# BitALU.net
KiCad netlist of a schematic drawn in EAGLE
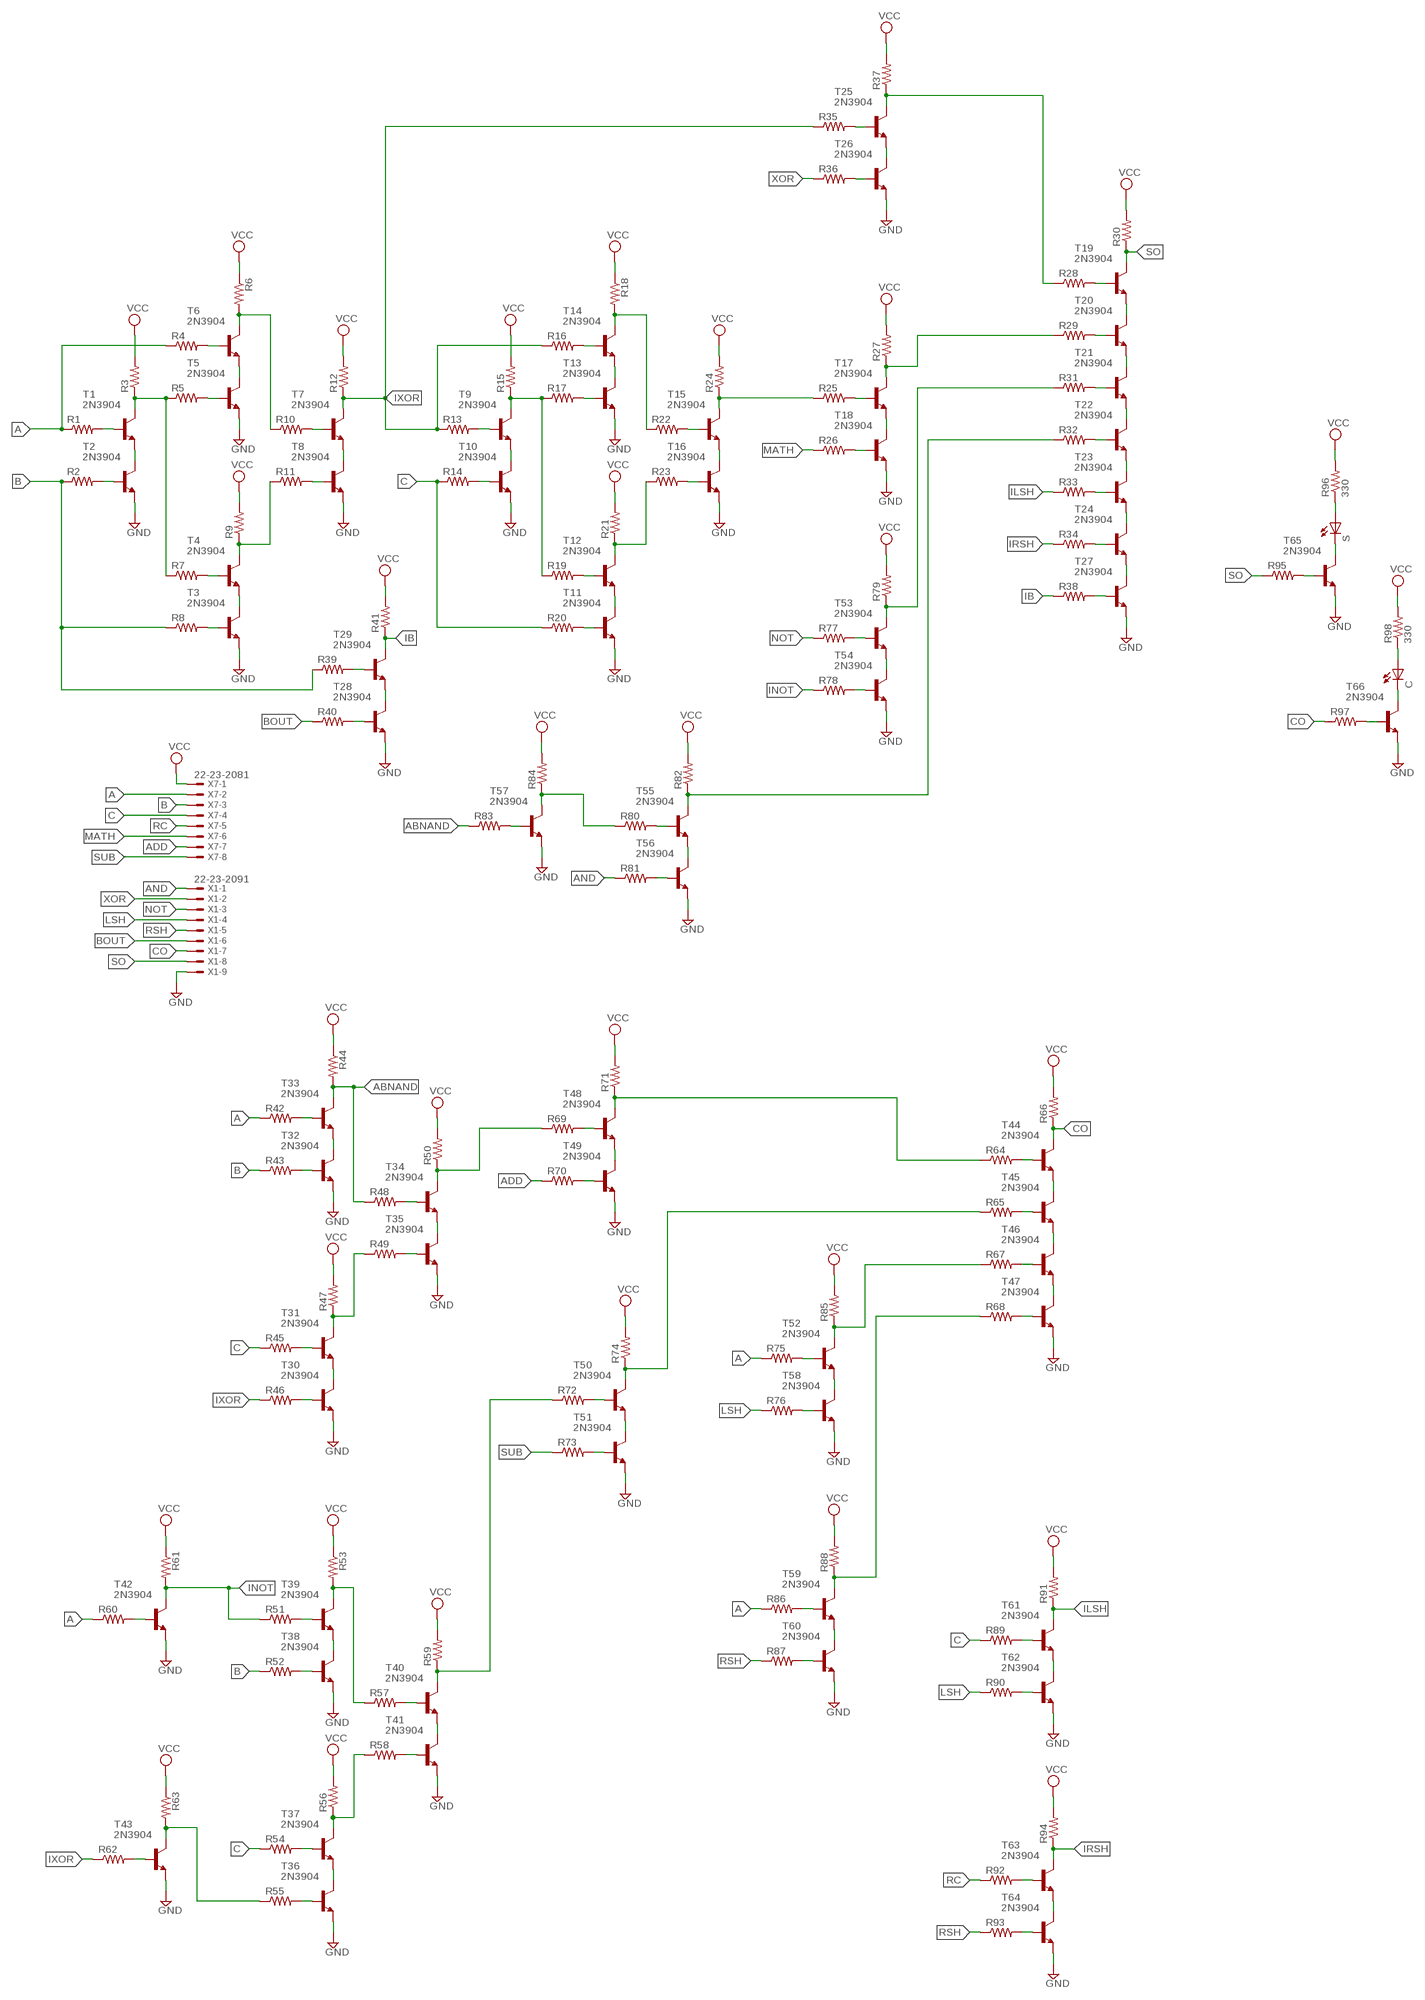
[diagram p0: schematic, sheet 1]

(export (version "E")
  (design (tool "Eeschema 10.0.6"))
  (components
    (comp (ref "C")
      (value "LED5MM")
      (footprint "eagle-import:LED5MM")
      (libsource (lib "eagle-import") (part "LED5MM"))
    )
    (comp (ref "R1")
      (value "R-US_0309/10")
      (footprint "eagle-import:0309_10")
      (libsource (lib "eagle-import") (part "R-US_0309/10"))
    )
    (comp (ref "R2")
      (value "R-US_0309/10")
      (footprint "eagle-import:0309_10")
      (libsource (lib "eagle-import") (part "R-US_0309/10"))
    )
    (comp (ref "R3")
      (value "R-US_0309/10")
      (footprint "eagle-import:0309_10")
      (libsource (lib "eagle-import") (part "R-US_0309/10"))
    )
    (comp (ref "R4")
      (value "R-US_0309/10")
      (footprint "eagle-import:0309_10")
      (libsource (lib "eagle-import") (part "R-US_0309/10"))
    )
    (comp (ref "R5")
      (value "R-US_0309/10")
      (footprint "eagle-import:0309_10")
      (libsource (lib "eagle-import") (part "R-US_0309/10"))
    )
    (comp (ref "R6")
      (value "R-US_0309/10")
      (footprint "eagle-import:0309_10")
      (libsource (lib "eagle-import") (part "R-US_0309/10"))
    )
    (comp (ref "R7")
      (value "R-US_0309/10")
      (footprint "eagle-import:0309_10")
      (libsource (lib "eagle-import") (part "R-US_0309/10"))
    )
    (comp (ref "R8")
      (value "R-US_0309/10")
      (footprint "eagle-import:0309_10")
      (libsource (lib "eagle-import") (part "R-US_0309/10"))
    )
    (comp (ref "R9")
      (value "R-US_0309/10")
      (footprint "eagle-import:0309_10")
      (libsource (lib "eagle-import") (part "R-US_0309/10"))
    )
    (comp (ref "R10")
      (value "R-US_0309/10")
      (footprint "eagle-import:0309_10")
      (libsource (lib "eagle-import") (part "R-US_0309/10"))
    )
    (comp (ref "R11")
      (value "R-US_0309/10")
      (footprint "eagle-import:0309_10")
      (libsource (lib "eagle-import") (part "R-US_0309/10"))
    )
    (comp (ref "R12")
      (value "R-US_0309/10")
      (footprint "eagle-import:0309_10")
      (libsource (lib "eagle-import") (part "R-US_0309/10"))
    )
    (comp (ref "R13")
      (value "R-US_0309/10")
      (footprint "eagle-import:0309_10")
      (libsource (lib "eagle-import") (part "R-US_0309/10"))
    )
    (comp (ref "R14")
      (value "R-US_0309/10")
      (footprint "eagle-import:0309_10")
      (libsource (lib "eagle-import") (part "R-US_0309/10"))
    )
    (comp (ref "R15")
      (value "R-US_0309/10")
      (footprint "eagle-import:0309_10")
      (libsource (lib "eagle-import") (part "R-US_0309/10"))
    )
    (comp (ref "R16")
      (value "R-US_0309/10")
      (footprint "eagle-import:0309_10")
      (libsource (lib "eagle-import") (part "R-US_0309/10"))
    )
    (comp (ref "R17")
      (value "R-US_0309/10")
      (footprint "eagle-import:0309_10")
      (libsource (lib "eagle-import") (part "R-US_0309/10"))
    )
    (comp (ref "R18")
      (value "R-US_0309/10")
      (footprint "eagle-import:0309_10")
      (libsource (lib "eagle-import") (part "R-US_0309/10"))
    )
    (comp (ref "R19")
      (value "R-US_0309/10")
      (footprint "eagle-import:0309_10")
      (libsource (lib "eagle-import") (part "R-US_0309/10"))
    )
    (comp (ref "R20")
      (value "R-US_0309/10")
      (footprint "eagle-import:0309_10")
      (libsource (lib "eagle-import") (part "R-US_0309/10"))
    )
    (comp (ref "R21")
      (value "R-US_0309/10")
      (footprint "eagle-import:0309_10")
      (libsource (lib "eagle-import") (part "R-US_0309/10"))
    )
    (comp (ref "R22")
      (value "R-US_0309/10")
      (footprint "eagle-import:0309_10")
      (libsource (lib "eagle-import") (part "R-US_0309/10"))
    )
    (comp (ref "R23")
      (value "R-US_0309/10")
      (footprint "eagle-import:0309_10")
      (libsource (lib "eagle-import") (part "R-US_0309/10"))
    )
    (comp (ref "R24")
      (value "R-US_0309/10")
      (footprint "eagle-import:0309_10")
      (libsource (lib "eagle-import") (part "R-US_0309/10"))
    )
    (comp (ref "R25")
      (value "R-US_0309/10")
      (footprint "eagle-import:0309_10")
      (libsource (lib "eagle-import") (part "R-US_0309/10"))
    )
    (comp (ref "R26")
      (value "R-US_0309/10")
      (footprint "eagle-import:0309_10")
      (libsource (lib "eagle-import") (part "R-US_0309/10"))
    )
    (comp (ref "R27")
      (value "R-US_0309/10")
      (footprint "eagle-import:0309_10")
      (libsource (lib "eagle-import") (part "R-US_0309/10"))
    )
    (comp (ref "R28")
      (value "R-US_0309/10")
      (footprint "eagle-import:0309_10")
      (libsource (lib "eagle-import") (part "R-US_0309/10"))
    )
    (comp (ref "R29")
      (value "R-US_0309/10")
      (footprint "eagle-import:0309_10")
      (libsource (lib "eagle-import") (part "R-US_0309/10"))
    )
    (comp (ref "R30")
      (value "R-US_0309/10")
      (footprint "eagle-import:0309_10")
      (libsource (lib "eagle-import") (part "R-US_0309/10"))
    )
    (comp (ref "R31")
      (value "R-US_0309/10")
      (footprint "eagle-import:0309_10")
      (libsource (lib "eagle-import") (part "R-US_0309/10"))
    )
    (comp (ref "R32")
      (value "R-US_0309/10")
      (footprint "eagle-import:0309_10")
      (libsource (lib "eagle-import") (part "R-US_0309/10"))
    )
    (comp (ref "R33")
      (value "R-US_0309/10")
      (footprint "eagle-import:0309_10")
      (libsource (lib "eagle-import") (part "R-US_0309/10"))
    )
    (comp (ref "R34")
      (value "R-US_0309/10")
      (footprint "eagle-import:0309_10")
      (libsource (lib "eagle-import") (part "R-US_0309/10"))
    )
    (comp (ref "R35")
      (value "R-US_0309/10")
      (footprint "eagle-import:0309_10")
      (libsource (lib "eagle-import") (part "R-US_0309/10"))
    )
    (comp (ref "R36")
      (value "R-US_0309/10")
      (footprint "eagle-import:0309_10")
      (libsource (lib "eagle-import") (part "R-US_0309/10"))
    )
    (comp (ref "R37")
      (value "R-US_0309/10")
      (footprint "eagle-import:0309_10")
      (libsource (lib "eagle-import") (part "R-US_0309/10"))
    )
    (comp (ref "R38")
      (value "R-US_0309/10")
      (footprint "eagle-import:0309_10")
      (libsource (lib "eagle-import") (part "R-US_0309/10"))
    )
    (comp (ref "R39")
      (value "R-US_0309/10")
      (footprint "eagle-import:0309_10")
      (libsource (lib "eagle-import") (part "R-US_0309/10"))
    )
    (comp (ref "R40")
      (value "R-US_0309/10")
      (footprint "eagle-import:0309_10")
      (libsource (lib "eagle-import") (part "R-US_0309/10"))
    )
    (comp (ref "R41")
      (value "R-US_0309/10")
      (footprint "eagle-import:0309_10")
      (libsource (lib "eagle-import") (part "R-US_0309/10"))
    )
    (comp (ref "R42")
      (value "R-US_0309/10")
      (footprint "eagle-import:0309_10")
      (libsource (lib "eagle-import") (part "R-US_0309/10"))
    )
    (comp (ref "R43")
      (value "R-US_0309/10")
      (footprint "eagle-import:0309_10")
      (libsource (lib "eagle-import") (part "R-US_0309/10"))
    )
    (comp (ref "R44")
      (value "R-US_0309/10")
      (footprint "eagle-import:0309_10")
      (libsource (lib "eagle-import") (part "R-US_0309/10"))
    )
    (comp (ref "R45")
      (value "R-US_0309/10")
      (footprint "eagle-import:0309_10")
      (libsource (lib "eagle-import") (part "R-US_0309/10"))
    )
    (comp (ref "R46")
      (value "R-US_0309/10")
      (footprint "eagle-import:0309_10")
      (libsource (lib "eagle-import") (part "R-US_0309/10"))
    )
    (comp (ref "R47")
      (value "R-US_0309/10")
      (footprint "eagle-import:0309_10")
      (libsource (lib "eagle-import") (part "R-US_0309/10"))
    )
    (comp (ref "R48")
      (value "R-US_0309/10")
      (footprint "eagle-import:0309_10")
      (libsource (lib "eagle-import") (part "R-US_0309/10"))
    )
    (comp (ref "R49")
      (value "R-US_0309/10")
      (footprint "eagle-import:0309_10")
      (libsource (lib "eagle-import") (part "R-US_0309/10"))
    )
    (comp (ref "R50")
      (value "R-US_0309/10")
      (footprint "eagle-import:0309_10")
      (libsource (lib "eagle-import") (part "R-US_0309/10"))
    )
    (comp (ref "R51")
      (value "R-US_0309/10")
      (footprint "eagle-import:0309_10")
      (libsource (lib "eagle-import") (part "R-US_0309/10"))
    )
    (comp (ref "R52")
      (value "R-US_0309/10")
      (footprint "eagle-import:0309_10")
      (libsource (lib "eagle-import") (part "R-US_0309/10"))
    )
    (comp (ref "R53")
      (value "R-US_0309/10")
      (footprint "eagle-import:0309_10")
      (libsource (lib "eagle-import") (part "R-US_0309/10"))
    )
    (comp (ref "R54")
      (value "R-US_0309/10")
      (footprint "eagle-import:0309_10")
      (libsource (lib "eagle-import") (part "R-US_0309/10"))
    )
    (comp (ref "R55")
      (value "R-US_0309/10")
      (footprint "eagle-import:0309_10")
      (libsource (lib "eagle-import") (part "R-US_0309/10"))
    )
    (comp (ref "R56")
      (value "R-US_0309/10")
      (footprint "eagle-import:0309_10")
      (libsource (lib "eagle-import") (part "R-US_0309/10"))
    )
    (comp (ref "R57")
      (value "R-US_0309/10")
      (footprint "eagle-import:0309_10")
      (libsource (lib "eagle-import") (part "R-US_0309/10"))
    )
    (comp (ref "R58")
      (value "R-US_0309/10")
      (footprint "eagle-import:0309_10")
      (libsource (lib "eagle-import") (part "R-US_0309/10"))
    )
    (comp (ref "R59")
      (value "R-US_0309/10")
      (footprint "eagle-import:0309_10")
      (libsource (lib "eagle-import") (part "R-US_0309/10"))
    )
    (comp (ref "R60")
      (value "R-US_0309/10")
      (footprint "eagle-import:0309_10")
      (libsource (lib "eagle-import") (part "R-US_0309/10"))
    )
    (comp (ref "R61")
      (value "R-US_0309/10")
      (footprint "eagle-import:0309_10")
      (libsource (lib "eagle-import") (part "R-US_0309/10"))
    )
    (comp (ref "R62")
      (value "R-US_0309/10")
      (footprint "eagle-import:0309_10")
      (libsource (lib "eagle-import") (part "R-US_0309/10"))
    )
    (comp (ref "R63")
      (value "R-US_0309/10")
      (footprint "eagle-import:0309_10")
      (libsource (lib "eagle-import") (part "R-US_0309/10"))
    )
    (comp (ref "R64")
      (value "R-US_0309/10")
      (footprint "eagle-import:0309_10")
      (libsource (lib "eagle-import") (part "R-US_0309/10"))
    )
    (comp (ref "R65")
      (value "R-US_0309/10")
      (footprint "eagle-import:0309_10")
      (libsource (lib "eagle-import") (part "R-US_0309/10"))
    )
    (comp (ref "R66")
      (value "R-US_0309/10")
      (footprint "eagle-import:0309_10")
      (libsource (lib "eagle-import") (part "R-US_0309/10"))
    )
    (comp (ref "R67")
      (value "R-US_0309/10")
      (footprint "eagle-import:0309_10")
      (libsource (lib "eagle-import") (part "R-US_0309/10"))
    )
    (comp (ref "R68")
      (value "R-US_0309/10")
      (footprint "eagle-import:0309_10")
      (libsource (lib "eagle-import") (part "R-US_0309/10"))
    )
    (comp (ref "R69")
      (value "R-US_0309/10")
      (footprint "eagle-import:0309_10")
      (libsource (lib "eagle-import") (part "R-US_0309/10"))
    )
    (comp (ref "R70")
      (value "R-US_0309/10")
      (footprint "eagle-import:0309_10")
      (libsource (lib "eagle-import") (part "R-US_0309/10"))
    )
    (comp (ref "R71")
      (value "R-US_0309/10")
      (footprint "eagle-import:0309_10")
      (libsource (lib "eagle-import") (part "R-US_0309/10"))
    )
    (comp (ref "R72")
      (value "R-US_0309/10")
      (footprint "eagle-import:0309_10")
      (libsource (lib "eagle-import") (part "R-US_0309/10"))
    )
    (comp (ref "R73")
      (value "R-US_0309/10")
      (footprint "eagle-import:0309_10")
      (libsource (lib "eagle-import") (part "R-US_0309/10"))
    )
    (comp (ref "R74")
      (value "R-US_0309/10")
      (footprint "eagle-import:0309_10")
      (libsource (lib "eagle-import") (part "R-US_0309/10"))
    )
    (comp (ref "R75")
      (value "R-US_0309/10")
      (footprint "eagle-import:0309_10")
      (libsource (lib "eagle-import") (part "R-US_0309/10"))
    )
    (comp (ref "R76")
      (value "R-US_0309/10")
      (footprint "eagle-import:0309_10")
      (libsource (lib "eagle-import") (part "R-US_0309/10"))
    )
    (comp (ref "R77")
      (value "R-US_0309/10")
      (footprint "eagle-import:0309_10")
      (libsource (lib "eagle-import") (part "R-US_0309/10"))
    )
    (comp (ref "R78")
      (value "R-US_0309/10")
      (footprint "eagle-import:0309_10")
      (libsource (lib "eagle-import") (part "R-US_0309/10"))
    )
    (comp (ref "R79")
      (value "R-US_0309/10")
      (footprint "eagle-import:0309_10")
      (libsource (lib "eagle-import") (part "R-US_0309/10"))
    )
    (comp (ref "R80")
      (value "R-US_0309/10")
      (footprint "eagle-import:0309_10")
      (libsource (lib "eagle-import") (part "R-US_0309/10"))
    )
    (comp (ref "R81")
      (value "R-US_0309/10")
      (footprint "eagle-import:0309_10")
      (libsource (lib "eagle-import") (part "R-US_0309/10"))
    )
    (comp (ref "R82")
      (value "R-US_0309/10")
      (footprint "eagle-import:0309_10")
      (libsource (lib "eagle-import") (part "R-US_0309/10"))
    )
    (comp (ref "R83")
      (value "R-US_0309/10")
      (footprint "eagle-import:0309_10")
      (libsource (lib "eagle-import") (part "R-US_0309/10"))
    )
    (comp (ref "R84")
      (value "R-US_0309/10")
      (footprint "eagle-import:0309_10")
      (libsource (lib "eagle-import") (part "R-US_0309/10"))
    )
    (comp (ref "R85")
      (value "R-US_0309/10")
      (footprint "eagle-import:0309_10")
      (libsource (lib "eagle-import") (part "R-US_0309/10"))
    )
    (comp (ref "R86")
      (value "R-US_0309/10")
      (footprint "eagle-import:0309_10")
      (libsource (lib "eagle-import") (part "R-US_0309/10"))
    )
    (comp (ref "R87")
      (value "R-US_0309/10")
      (footprint "eagle-import:0309_10")
      (libsource (lib "eagle-import") (part "R-US_0309/10"))
    )
    (comp (ref "R88")
      (value "R-US_0309/10")
      (footprint "eagle-import:0309_10")
      (libsource (lib "eagle-import") (part "R-US_0309/10"))
    )
    (comp (ref "R89")
      (value "R-US_0309/10")
      (footprint "eagle-import:0309_10")
      (libsource (lib "eagle-import") (part "R-US_0309/10"))
    )
    (comp (ref "R90")
      (value "R-US_0309/10")
      (footprint "eagle-import:0309_10")
      (libsource (lib "eagle-import") (part "R-US_0309/10"))
    )
    (comp (ref "R91")
      (value "R-US_0309/10")
      (footprint "eagle-import:0309_10")
      (libsource (lib "eagle-import") (part "R-US_0309/10"))
    )
    (comp (ref "R92")
      (value "R-US_0309/10")
      (footprint "eagle-import:0309_10")
      (libsource (lib "eagle-import") (part "R-US_0309/10"))
    )
    (comp (ref "R93")
      (value "R-US_0309/10")
      (footprint "eagle-import:0309_10")
      (libsource (lib "eagle-import") (part "R-US_0309/10"))
    )
    (comp (ref "R94")
      (value "R-US_0309/10")
      (footprint "eagle-import:0309_10")
      (libsource (lib "eagle-import") (part "R-US_0309/10"))
    )
    (comp (ref "R95")
      (value "R-US_0309/10")
      (footprint "eagle-import:0309_10")
      (libsource (lib "eagle-import") (part "R-US_0309/10"))
    )
    (comp (ref "R96")
      (value "330")
      (footprint "eagle-import:0309_10")
      (libsource (lib "eagle-import") (part "R-US_0309/10"))
    )
    (comp (ref "R97")
      (value "R-US_0309/10")
      (footprint "eagle-import:0309_10")
      (libsource (lib "eagle-import") (part "R-US_0309/10"))
    )
    (comp (ref "R98")
      (value "330")
      (footprint "eagle-import:0309_10")
      (libsource (lib "eagle-import") (part "R-US_0309/10"))
    )
    (comp (ref "S")
      (value "LED5MM")
      (footprint "eagle-import:LED5MM")
      (libsource (lib "eagle-import") (part "LED5MM"))
    )
    (comp (ref "T1")
      (value "2N3904")
      (footprint "eagle-import:TO92")
      (libsource (lib "eagle-import") (part "2N3904"))
    )
    (comp (ref "T2")
      (value "2N3904")
      (footprint "eagle-import:TO92")
      (libsource (lib "eagle-import") (part "2N3904"))
    )
    (comp (ref "T3")
      (value "2N3904")
      (footprint "eagle-import:TO92")
      (libsource (lib "eagle-import") (part "2N3904"))
    )
    (comp (ref "T4")
      (value "2N3904")
      (footprint "eagle-import:TO92")
      (libsource (lib "eagle-import") (part "2N3904"))
    )
    (comp (ref "T5")
      (value "2N3904")
      (footprint "eagle-import:TO92")
      (libsource (lib "eagle-import") (part "2N3904"))
    )
    (comp (ref "T6")
      (value "2N3904")
      (footprint "eagle-import:TO92")
      (libsource (lib "eagle-import") (part "2N3904"))
    )
    (comp (ref "T7")
      (value "2N3904")
      (footprint "eagle-import:TO92")
      (libsource (lib "eagle-import") (part "2N3904"))
    )
    (comp (ref "T8")
      (value "2N3904")
      (footprint "eagle-import:TO92")
      (libsource (lib "eagle-import") (part "2N3904"))
    )
    (comp (ref "T9")
      (value "2N3904")
      (footprint "eagle-import:TO92")
      (libsource (lib "eagle-import") (part "2N3904"))
    )
    (comp (ref "T10")
      (value "2N3904")
      (footprint "eagle-import:TO92")
      (libsource (lib "eagle-import") (part "2N3904"))
    )
    (comp (ref "T11")
      (value "2N3904")
      (footprint "eagle-import:TO92")
      (libsource (lib "eagle-import") (part "2N3904"))
    )
    (comp (ref "T12")
      (value "2N3904")
      (footprint "eagle-import:TO92")
      (libsource (lib "eagle-import") (part "2N3904"))
    )
    (comp (ref "T13")
      (value "2N3904")
      (footprint "eagle-import:TO92")
      (libsource (lib "eagle-import") (part "2N3904"))
    )
    (comp (ref "T14")
      (value "2N3904")
      (footprint "eagle-import:TO92")
      (libsource (lib "eagle-import") (part "2N3904"))
    )
    (comp (ref "T15")
      (value "2N3904")
      (footprint "eagle-import:TO92")
      (libsource (lib "eagle-import") (part "2N3904"))
    )
    (comp (ref "T16")
      (value "2N3904")
      (footprint "eagle-import:TO92")
      (libsource (lib "eagle-import") (part "2N3904"))
    )
    (comp (ref "T17")
      (value "2N3904")
      (footprint "eagle-import:TO92")
      (libsource (lib "eagle-import") (part "2N3904"))
    )
    (comp (ref "T18")
      (value "2N3904")
      (footprint "eagle-import:TO92")
      (libsource (lib "eagle-import") (part "2N3904"))
    )
    (comp (ref "T19")
      (value "2N3904")
      (footprint "eagle-import:TO92")
      (libsource (lib "eagle-import") (part "2N3904"))
    )
    (comp (ref "T20")
      (value "2N3904")
      (footprint "eagle-import:TO92")
      (libsource (lib "eagle-import") (part "2N3904"))
    )
    (comp (ref "T21")
      (value "2N3904")
      (footprint "eagle-import:TO92")
      (libsource (lib "eagle-import") (part "2N3904"))
    )
    (comp (ref "T22")
      (value "2N3904")
      (footprint "eagle-import:TO92")
      (libsource (lib "eagle-import") (part "2N3904"))
    )
    (comp (ref "T23")
      (value "2N3904")
      (footprint "eagle-import:TO92")
      (libsource (lib "eagle-import") (part "2N3904"))
    )
    (comp (ref "T24")
      (value "2N3904")
      (footprint "eagle-import:TO92")
      (libsource (lib "eagle-import") (part "2N3904"))
    )
    (comp (ref "T25")
      (value "2N3904")
      (footprint "eagle-import:TO92")
      (libsource (lib "eagle-import") (part "2N3904"))
    )
    (comp (ref "T26")
      (value "2N3904")
      (footprint "eagle-import:TO92")
      (libsource (lib "eagle-import") (part "2N3904"))
    )
    (comp (ref "T27")
      (value "2N3904")
      (footprint "eagle-import:TO92")
      (libsource (lib "eagle-import") (part "2N3904"))
    )
    (comp (ref "T28")
      (value "2N3904")
      (footprint "eagle-import:TO92")
      (libsource (lib "eagle-import") (part "2N3904"))
    )
    (comp (ref "T29")
      (value "2N3904")
      (footprint "eagle-import:TO92")
      (libsource (lib "eagle-import") (part "2N3904"))
    )
    (comp (ref "T30")
      (value "2N3904")
      (footprint "eagle-import:TO92")
      (libsource (lib "eagle-import") (part "2N3904"))
    )
    (comp (ref "T31")
      (value "2N3904")
      (footprint "eagle-import:TO92")
      (libsource (lib "eagle-import") (part "2N3904"))
    )
    (comp (ref "T32")
      (value "2N3904")
      (footprint "eagle-import:TO92")
      (libsource (lib "eagle-import") (part "2N3904"))
    )
    (comp (ref "T33")
      (value "2N3904")
      (footprint "eagle-import:TO92")
      (libsource (lib "eagle-import") (part "2N3904"))
    )
    (comp (ref "T34")
      (value "2N3904")
      (footprint "eagle-import:TO92")
      (libsource (lib "eagle-import") (part "2N3904"))
    )
    (comp (ref "T35")
      (value "2N3904")
      (footprint "eagle-import:TO92")
      (libsource (lib "eagle-import") (part "2N3904"))
    )
    (comp (ref "T36")
      (value "2N3904")
      (footprint "eagle-import:TO92")
      (libsource (lib "eagle-import") (part "2N3904"))
    )
    (comp (ref "T37")
      (value "2N3904")
      (footprint "eagle-import:TO92")
      (libsource (lib "eagle-import") (part "2N3904"))
    )
    (comp (ref "T38")
      (value "2N3904")
      (footprint "eagle-import:TO92")
      (libsource (lib "eagle-import") (part "2N3904"))
    )
    (comp (ref "T39")
      (value "2N3904")
      (footprint "eagle-import:TO92")
      (libsource (lib "eagle-import") (part "2N3904"))
    )
    (comp (ref "T40")
      (value "2N3904")
      (footprint "eagle-import:TO92")
      (libsource (lib "eagle-import") (part "2N3904"))
    )
    (comp (ref "T41")
      (value "2N3904")
      (footprint "eagle-import:TO92")
      (libsource (lib "eagle-import") (part "2N3904"))
    )
    (comp (ref "T42")
      (value "2N3904")
      (footprint "eagle-import:TO92")
      (libsource (lib "eagle-import") (part "2N3904"))
    )
    (comp (ref "T43")
      (value "2N3904")
      (footprint "eagle-import:TO92")
      (libsource (lib "eagle-import") (part "2N3904"))
    )
    (comp (ref "T44")
      (value "2N3904")
      (footprint "eagle-import:TO92")
      (libsource (lib "eagle-import") (part "2N3904"))
    )
    (comp (ref "T45")
      (value "2N3904")
      (footprint "eagle-import:TO92")
      (libsource (lib "eagle-import") (part "2N3904"))
    )
    (comp (ref "T46")
      (value "2N3904")
      (footprint "eagle-import:TO92")
      (libsource (lib "eagle-import") (part "2N3904"))
    )
    (comp (ref "T47")
      (value "2N3904")
      (footprint "eagle-import:TO92")
      (libsource (lib "eagle-import") (part "2N3904"))
    )
    (comp (ref "T48")
      (value "2N3904")
      (footprint "eagle-import:TO92")
      (libsource (lib "eagle-import") (part "2N3904"))
    )
    (comp (ref "T49")
      (value "2N3904")
      (footprint "eagle-import:TO92")
      (libsource (lib "eagle-import") (part "2N3904"))
    )
    (comp (ref "T50")
      (value "2N3904")
      (footprint "eagle-import:TO92")
      (libsource (lib "eagle-import") (part "2N3904"))
    )
    (comp (ref "T51")
      (value "2N3904")
      (footprint "eagle-import:TO92")
      (libsource (lib "eagle-import") (part "2N3904"))
    )
    (comp (ref "T52")
      (value "2N3904")
      (footprint "eagle-import:TO92")
      (libsource (lib "eagle-import") (part "2N3904"))
    )
    (comp (ref "T53")
      (value "2N3904")
      (footprint "eagle-import:TO92")
      (libsource (lib "eagle-import") (part "2N3904"))
    )
    (comp (ref "T54")
      (value "2N3904")
      (footprint "eagle-import:TO92")
      (libsource (lib "eagle-import") (part "2N3904"))
    )
    (comp (ref "T55")
      (value "2N3904")
      (footprint "eagle-import:TO92")
      (libsource (lib "eagle-import") (part "2N3904"))
    )
    (comp (ref "T56")
      (value "2N3904")
      (footprint "eagle-import:TO92")
      (libsource (lib "eagle-import") (part "2N3904"))
    )
    (comp (ref "T57")
      (value "2N3904")
      (footprint "eagle-import:TO92")
      (libsource (lib "eagle-import") (part "2N3904"))
    )
    (comp (ref "T58")
      (value "2N3904")
      (footprint "eagle-import:TO92")
      (libsource (lib "eagle-import") (part "2N3904"))
    )
    (comp (ref "T59")
      (value "2N3904")
      (footprint "eagle-import:TO92")
      (libsource (lib "eagle-import") (part "2N3904"))
    )
    (comp (ref "T60")
      (value "2N3904")
      (footprint "eagle-import:TO92")
      (libsource (lib "eagle-import") (part "2N3904"))
    )
    (comp (ref "T61")
      (value "2N3904")
      (footprint "eagle-import:TO92")
      (libsource (lib "eagle-import") (part "2N3904"))
    )
    (comp (ref "T62")
      (value "2N3904")
      (footprint "eagle-import:TO92")
      (libsource (lib "eagle-import") (part "2N3904"))
    )
    (comp (ref "T63")
      (value "2N3904")
      (footprint "eagle-import:TO92")
      (libsource (lib "eagle-import") (part "2N3904"))
    )
    (comp (ref "T64")
      (value "2N3904")
      (footprint "eagle-import:TO92")
      (libsource (lib "eagle-import") (part "2N3904"))
    )
    (comp (ref "T65")
      (value "2N3904")
      (footprint "eagle-import:TO92")
      (libsource (lib "eagle-import") (part "2N3904"))
    )
    (comp (ref "T66")
      (value "2N3904")
      (footprint "eagle-import:TO92")
      (libsource (lib "eagle-import") (part "2N3904"))
    )
    (comp (ref "X1")
      (value "22-23-2091")
      (footprint "eagle-import:22-23-2091")
      (fields (field (name "MF") "MOLEX"))
      (libsource (lib "eagle-import") (part "22-23-2091"))
    )
    (comp (ref "X7")
      (value "22-23-2081")
      (footprint "eagle-import:22-23-2081")
      (fields (field (name "MF") "MOLEX"))
      (libsource (lib "eagle-import") (part "22-23-2081"))
    )
  )
  (nets
    (net (code "1") (name "A") (class "Default")
      (node (ref "R1") (pin "1") (pinfunction "1_1") (pintype "passive"))
      (node (ref "R4") (pin "1") (pinfunction "1_1") (pintype "passive"))
      (node (ref "R42") (pin "1") (pinfunction "1_1") (pintype "passive"))
      (node (ref "R60") (pin "1") (pinfunction "1_1") (pintype "passive"))
      (node (ref "R75") (pin "1") (pinfunction "1_1") (pintype "passive"))
      (node (ref "R86") (pin "1") (pinfunction "1_1") (pintype "passive"))
      (node (ref "X7") (pin "2") (pinfunction "S_2") (pintype "passive"))
    )
    (net (code "2") (name "ABNAND") (class "Default")
      (node (ref "R44") (pin "2") (pinfunction "2_2") (pintype "passive"))
      (node (ref "R48") (pin "1") (pinfunction "1_1") (pintype "passive"))
      (node (ref "R83") (pin "1") (pinfunction "1_1") (pintype "passive"))
      (node (ref "T33") (pin "1") (pinfunction "C_1") (pintype "passive"))
    )
    (net (code "3") (name "ADD") (class "Default")
      (node (ref "R70") (pin "1") (pinfunction "1_1") (pintype "passive"))
      (node (ref "X7") (pin "7") (pinfunction "S_7") (pintype "passive"))
    )
    (net (code "4") (name "AND") (class "Default")
      (node (ref "R81") (pin "1") (pinfunction "1_1") (pintype "passive"))
      (node (ref "X1") (pin "1") (pinfunction "S_1") (pintype "passive"))
    )
    (net (code "5") (name "B") (class "Default")
      (node (ref "R2") (pin "1") (pinfunction "1_1") (pintype "passive"))
      (node (ref "R39") (pin "1") (pinfunction "1_1") (pintype "passive"))
      (node (ref "R43") (pin "1") (pinfunction "1_1") (pintype "passive"))
      (node (ref "R52") (pin "1") (pinfunction "1_1") (pintype "passive"))
      (node (ref "R8") (pin "1") (pinfunction "1_1") (pintype "passive"))
      (node (ref "X7") (pin "3") (pinfunction "S_3") (pintype "passive"))
    )
    (net (code "6") (name "BOUT") (class "Default")
      (node (ref "R40") (pin "1") (pinfunction "1_1") (pintype "passive"))
      (node (ref "X1") (pin "6") (pinfunction "S_6") (pintype "passive"))
    )
    (net (code "7") (name "C") (class "Default")
      (node (ref "R14") (pin "1") (pinfunction "1_1") (pintype "passive"))
      (node (ref "R20") (pin "1") (pinfunction "1_1") (pintype "passive"))
      (node (ref "R45") (pin "1") (pinfunction "1_1") (pintype "passive"))
      (node (ref "R54") (pin "1") (pinfunction "1_1") (pintype "passive"))
      (node (ref "R89") (pin "1") (pinfunction "1_1") (pintype "passive"))
      (node (ref "X7") (pin "4") (pinfunction "S_4") (pintype "passive"))
    )
    (net (code "8") (name "CO") (class "Default")
      (node (ref "R66") (pin "1") (pinfunction "1_1") (pintype "passive"))
      (node (ref "R97") (pin "1") (pinfunction "1_1") (pintype "passive"))
      (node (ref "T44") (pin "1") (pinfunction "C_1") (pintype "passive"))
      (node (ref "X1") (pin "7") (pinfunction "S_7") (pintype "passive"))
    )
    (net (code "9") (name "GND") (class "Default")
      (node (ref "T10") (pin "3") (pinfunction "E_3") (pintype "passive"))
      (node (ref "T11") (pin "3") (pinfunction "E_3") (pintype "passive"))
      (node (ref "T13") (pin "3") (pinfunction "E_3") (pintype "passive"))
      (node (ref "T16") (pin "3") (pinfunction "E_3") (pintype "passive"))
      (node (ref "T18") (pin "3") (pinfunction "E_3") (pintype "passive"))
      (node (ref "T2") (pin "3") (pinfunction "E_3") (pintype "passive"))
      (node (ref "T26") (pin "3") (pinfunction "E_3") (pintype "passive"))
      (node (ref "T27") (pin "3") (pinfunction "E_3") (pintype "passive"))
      (node (ref "T28") (pin "3") (pinfunction "E_3") (pintype "passive"))
      (node (ref "T3") (pin "3") (pinfunction "E_3") (pintype "passive"))
      (node (ref "T30") (pin "3") (pinfunction "E_3") (pintype "passive"))
      (node (ref "T32") (pin "3") (pinfunction "E_3") (pintype "passive"))
      (node (ref "T35") (pin "3") (pinfunction "E_3") (pintype "passive"))
      (node (ref "T36") (pin "3") (pinfunction "E_3") (pintype "passive"))
      (node (ref "T38") (pin "3") (pinfunction "E_3") (pintype "passive"))
      (node (ref "T41") (pin "3") (pinfunction "E_3") (pintype "passive"))
      (node (ref "T42") (pin "3") (pinfunction "E_3") (pintype "passive"))
      (node (ref "T43") (pin "3") (pinfunction "E_3") (pintype "passive"))
      (node (ref "T47") (pin "3") (pinfunction "E_3") (pintype "passive"))
      (node (ref "T49") (pin "3") (pinfunction "E_3") (pintype "passive"))
      (node (ref "T5") (pin "3") (pinfunction "E_3") (pintype "passive"))
      (node (ref "T51") (pin "3") (pinfunction "E_3") (pintype "passive"))
      (node (ref "T54") (pin "3") (pinfunction "E_3") (pintype "passive"))
      (node (ref "T56") (pin "3") (pinfunction "E_3") (pintype "passive"))
      (node (ref "T57") (pin "3") (pinfunction "E_3") (pintype "passive"))
      (node (ref "T58") (pin "3") (pinfunction "E_3") (pintype "passive"))
      (node (ref "T60") (pin "3") (pinfunction "E_3") (pintype "passive"))
      (node (ref "T62") (pin "3") (pinfunction "E_3") (pintype "passive"))
      (node (ref "T64") (pin "3") (pinfunction "E_3") (pintype "passive"))
      (node (ref "T65") (pin "3") (pinfunction "E_3") (pintype "passive"))
      (node (ref "T66") (pin "3") (pinfunction "E_3") (pintype "passive"))
      (node (ref "T8") (pin "3") (pinfunction "E_3") (pintype "passive"))
      (node (ref "X1") (pin "9") (pinfunction "S_9") (pintype "passive"))
    )
    (net (code "10") (name "IB") (class "Default")
      (node (ref "R38") (pin "1") (pinfunction "1_1") (pintype "passive"))
      (node (ref "R41") (pin "1") (pinfunction "1_1") (pintype "passive"))
      (node (ref "T29") (pin "1") (pinfunction "C_1") (pintype "passive"))
    )
    (net (code "11") (name "ILSH") (class "Default")
      (node (ref "R33") (pin "1") (pinfunction "1_1") (pintype "passive"))
      (node (ref "R91") (pin "1") (pinfunction "1_1") (pintype "passive"))
      (node (ref "T61") (pin "1") (pinfunction "C_1") (pintype "passive"))
    )
    (net (code "12") (name "INOT") (class "Default")
      (node (ref "R51") (pin "1") (pinfunction "1_1") (pintype "passive"))
      (node (ref "R61") (pin "2") (pinfunction "2_2") (pintype "passive"))
      (node (ref "R78") (pin "1") (pinfunction "1_1") (pintype "passive"))
      (node (ref "T42") (pin "1") (pinfunction "C_1") (pintype "passive"))
    )
    (net (code "13") (name "IRSH") (class "Default")
      (node (ref "R34") (pin "1") (pinfunction "1_1") (pintype "passive"))
      (node (ref "R94") (pin "1") (pinfunction "1_1") (pintype "passive"))
      (node (ref "T63") (pin "1") (pinfunction "C_1") (pintype "passive"))
    )
    (net (code "14") (name "IXOR") (class "Default")
      (node (ref "R12") (pin "1") (pinfunction "1_1") (pintype "passive"))
      (node (ref "R13") (pin "1") (pinfunction "1_1") (pintype "passive"))
      (node (ref "R16") (pin "1") (pinfunction "1_1") (pintype "passive"))
      (node (ref "R35") (pin "1") (pinfunction "1_1") (pintype "passive"))
      (node (ref "R46") (pin "1") (pinfunction "1_1") (pintype "passive"))
      (node (ref "R62") (pin "1") (pinfunction "1_1") (pintype "passive"))
      (node (ref "T7") (pin "1") (pinfunction "C_1") (pintype "passive"))
    )
    (net (code "15") (name "LSH") (class "Default")
      (node (ref "R76") (pin "1") (pinfunction "1_1") (pintype "passive"))
      (node (ref "R90") (pin "1") (pinfunction "1_1") (pintype "passive"))
      (node (ref "X1") (pin "4") (pinfunction "S_4") (pintype "passive"))
    )
    (net (code "16") (name "MATH") (class "Default")
      (node (ref "R26") (pin "1") (pinfunction "1_1") (pintype "passive"))
      (node (ref "X7") (pin "6") (pinfunction "S_6") (pintype "passive"))
    )
    (net (code "17") (name "NOT") (class "Default")
      (node (ref "R77") (pin "1") (pinfunction "1_1") (pintype "passive"))
      (node (ref "X1") (pin "3") (pinfunction "S_3") (pintype "passive"))
    )
    (net (code "18") (name "Net-(C-C)") (class "Default")
      (node (ref "C") (pin "K") (pinfunction "C_K") (pintype "passive"))
      (node (ref "T66") (pin "1") (pinfunction "C_1") (pintype "passive"))
    )
    (net (code "19") (name "Net-(C-PadA)") (class "Default")
      (node (ref "C") (pin "A") (pinfunction "A_A") (pintype "passive"))
      (node (ref "R98") (pin "1") (pinfunction "1_1") (pintype "passive"))
    )
    (net (code "20") (name "Net-(R96-Pad1)") (class "Default")
      (node (ref "R96") (pin "1") (pinfunction "1_1") (pintype "passive"))
      (node (ref "S") (pin "A") (pinfunction "A_A") (pintype "passive"))
    )
    (net (code "21") (name "Net-(S-C)") (class "Default")
      (node (ref "S") (pin "K") (pinfunction "C_K") (pintype "passive"))
      (node (ref "T65") (pin "1") (pinfunction "C_1") (pintype "passive"))
    )
    (net (code "22") (name "Net-(T1-B)") (class "Default")
      (node (ref "R1") (pin "2") (pinfunction "2_2") (pintype "passive"))
      (node (ref "T1") (pin "2") (pinfunction "B_2") (pintype "passive"))
    )
    (net (code "23") (name "Net-(T1-C)") (class "Default")
      (node (ref "R3") (pin "1") (pinfunction "1_1") (pintype "passive"))
      (node (ref "R5") (pin "1") (pinfunction "1_1") (pintype "passive"))
      (node (ref "R7") (pin "1") (pinfunction "1_1") (pintype "passive"))
      (node (ref "T1") (pin "1") (pinfunction "C_1") (pintype "passive"))
    )
    (net (code "24") (name "Net-(T1-E)") (class "Default")
      (node (ref "T1") (pin "3") (pinfunction "E_3") (pintype "passive"))
      (node (ref "T2") (pin "1") (pinfunction "C_1") (pintype "passive"))
    )
    (net (code "25") (name "Net-(T2-B)") (class "Default")
      (node (ref "R2") (pin "2") (pinfunction "2_2") (pintype "passive"))
      (node (ref "T2") (pin "2") (pinfunction "B_2") (pintype "passive"))
    )
    (net (code "26") (name "Net-(T3-B)") (class "Default")
      (node (ref "R8") (pin "2") (pinfunction "2_2") (pintype "passive"))
      (node (ref "T3") (pin "2") (pinfunction "B_2") (pintype "passive"))
    )
    (net (code "27") (name "Net-(T3-C)") (class "Default")
      (node (ref "T3") (pin "1") (pinfunction "C_1") (pintype "passive"))
      (node (ref "T4") (pin "3") (pinfunction "E_3") (pintype "passive"))
    )
    (net (code "28") (name "Net-(T4-B)") (class "Default")
      (node (ref "R7") (pin "2") (pinfunction "2_2") (pintype "passive"))
      (node (ref "T4") (pin "2") (pinfunction "B_2") (pintype "passive"))
    )
    (net (code "29") (name "Net-(T4-C)") (class "Default")
      (node (ref "R11") (pin "1") (pinfunction "1_1") (pintype "passive"))
      (node (ref "R9") (pin "1") (pinfunction "1_1") (pintype "passive"))
      (node (ref "T4") (pin "1") (pinfunction "C_1") (pintype "passive"))
    )
    (net (code "30") (name "Net-(T5-B)") (class "Default")
      (node (ref "R5") (pin "2") (pinfunction "2_2") (pintype "passive"))
      (node (ref "T5") (pin "2") (pinfunction "B_2") (pintype "passive"))
    )
    (net (code "31") (name "Net-(T5-C)") (class "Default")
      (node (ref "T5") (pin "1") (pinfunction "C_1") (pintype "passive"))
      (node (ref "T6") (pin "3") (pinfunction "E_3") (pintype "passive"))
    )
    (net (code "32") (name "Net-(T6-B)") (class "Default")
      (node (ref "R4") (pin "2") (pinfunction "2_2") (pintype "passive"))
      (node (ref "T6") (pin "2") (pinfunction "B_2") (pintype "passive"))
    )
    (net (code "33") (name "Net-(T6-C)") (class "Default")
      (node (ref "R10") (pin "1") (pinfunction "1_1") (pintype "passive"))
      (node (ref "R6") (pin "2") (pinfunction "2_2") (pintype "passive"))
      (node (ref "T6") (pin "1") (pinfunction "C_1") (pintype "passive"))
    )
    (net (code "34") (name "Net-(T7-B)") (class "Default")
      (node (ref "R10") (pin "2") (pinfunction "2_2") (pintype "passive"))
      (node (ref "T7") (pin "2") (pinfunction "B_2") (pintype "passive"))
    )
    (net (code "35") (name "Net-(T7-E)") (class "Default")
      (node (ref "T7") (pin "3") (pinfunction "E_3") (pintype "passive"))
      (node (ref "T8") (pin "1") (pinfunction "C_1") (pintype "passive"))
    )
    (net (code "36") (name "Net-(T8-B)") (class "Default")
      (node (ref "R11") (pin "2") (pinfunction "2_2") (pintype "passive"))
      (node (ref "T8") (pin "2") (pinfunction "B_2") (pintype "passive"))
    )
    (net (code "37") (name "Net-(T9-B)") (class "Default")
      (node (ref "R13") (pin "2") (pinfunction "2_2") (pintype "passive"))
      (node (ref "T9") (pin "2") (pinfunction "B_2") (pintype "passive"))
    )
    (net (code "38") (name "Net-(T9-C)") (class "Default")
      (node (ref "R15") (pin "1") (pinfunction "1_1") (pintype "passive"))
      (node (ref "R17") (pin "1") (pinfunction "1_1") (pintype "passive"))
      (node (ref "R19") (pin "1") (pinfunction "1_1") (pintype "passive"))
      (node (ref "T9") (pin "1") (pinfunction "C_1") (pintype "passive"))
    )
    (net (code "39") (name "Net-(T10-B)") (class "Default")
      (node (ref "R14") (pin "2") (pinfunction "2_2") (pintype "passive"))
      (node (ref "T10") (pin "2") (pinfunction "B_2") (pintype "passive"))
    )
    (net (code "40") (name "Net-(T10-C)") (class "Default")
      (node (ref "T10") (pin "1") (pinfunction "C_1") (pintype "passive"))
      (node (ref "T9") (pin "3") (pinfunction "E_3") (pintype "passive"))
    )
    (net (code "41") (name "Net-(T11-B)") (class "Default")
      (node (ref "R20") (pin "2") (pinfunction "2_2") (pintype "passive"))
      (node (ref "T11") (pin "2") (pinfunction "B_2") (pintype "passive"))
    )
    (net (code "42") (name "Net-(T11-C)") (class "Default")
      (node (ref "T11") (pin "1") (pinfunction "C_1") (pintype "passive"))
      (node (ref "T12") (pin "3") (pinfunction "E_3") (pintype "passive"))
    )
    (net (code "43") (name "Net-(T12-B)") (class "Default")
      (node (ref "R19") (pin "2") (pinfunction "2_2") (pintype "passive"))
      (node (ref "T12") (pin "2") (pinfunction "B_2") (pintype "passive"))
    )
    (net (code "44") (name "Net-(T12-C)") (class "Default")
      (node (ref "R21") (pin "1") (pinfunction "1_1") (pintype "passive"))
      (node (ref "R23") (pin "1") (pinfunction "1_1") (pintype "passive"))
      (node (ref "T12") (pin "1") (pinfunction "C_1") (pintype "passive"))
    )
    (net (code "45") (name "Net-(T13-B)") (class "Default")
      (node (ref "R17") (pin "2") (pinfunction "2_2") (pintype "passive"))
      (node (ref "T13") (pin "2") (pinfunction "B_2") (pintype "passive"))
    )
    (net (code "46") (name "Net-(T13-C)") (class "Default")
      (node (ref "T13") (pin "1") (pinfunction "C_1") (pintype "passive"))
      (node (ref "T14") (pin "3") (pinfunction "E_3") (pintype "passive"))
    )
    (net (code "47") (name "Net-(T14-B)") (class "Default")
      (node (ref "R16") (pin "2") (pinfunction "2_2") (pintype "passive"))
      (node (ref "T14") (pin "2") (pinfunction "B_2") (pintype "passive"))
    )
    (net (code "48") (name "Net-(T14-C)") (class "Default")
      (node (ref "R18") (pin "2") (pinfunction "2_2") (pintype "passive"))
      (node (ref "R22") (pin "1") (pinfunction "1_1") (pintype "passive"))
      (node (ref "T14") (pin "1") (pinfunction "C_1") (pintype "passive"))
    )
    (net (code "49") (name "Net-(T15-B)") (class "Default")
      (node (ref "R22") (pin "2") (pinfunction "2_2") (pintype "passive"))
      (node (ref "T15") (pin "2") (pinfunction "B_2") (pintype "passive"))
    )
    (net (code "50") (name "Net-(T15-C)") (class "Default")
      (node (ref "R24") (pin "1") (pinfunction "1_1") (pintype "passive"))
      (node (ref "R25") (pin "1") (pinfunction "1_1") (pintype "passive"))
      (node (ref "T15") (pin "1") (pinfunction "C_1") (pintype "passive"))
    )
    (net (code "51") (name "Net-(T15-E)") (class "Default")
      (node (ref "T15") (pin "3") (pinfunction "E_3") (pintype "passive"))
      (node (ref "T16") (pin "1") (pinfunction "C_1") (pintype "passive"))
    )
    (net (code "52") (name "Net-(T16-B)") (class "Default")
      (node (ref "R23") (pin "2") (pinfunction "2_2") (pintype "passive"))
      (node (ref "T16") (pin "2") (pinfunction "B_2") (pintype "passive"))
    )
    (net (code "53") (name "Net-(T17-B)") (class "Default")
      (node (ref "R25") (pin "2") (pinfunction "2_2") (pintype "passive"))
      (node (ref "T17") (pin "2") (pinfunction "B_2") (pintype "passive"))
    )
    (net (code "54") (name "Net-(T17-C)") (class "Default")
      (node (ref "R27") (pin "1") (pinfunction "1_1") (pintype "passive"))
      (node (ref "R29") (pin "1") (pinfunction "1_1") (pintype "passive"))
      (node (ref "T17") (pin "1") (pinfunction "C_1") (pintype "passive"))
    )
    (net (code "55") (name "Net-(T17-E)") (class "Default")
      (node (ref "T17") (pin "3") (pinfunction "E_3") (pintype "passive"))
      (node (ref "T18") (pin "1") (pinfunction "C_1") (pintype "passive"))
    )
    (net (code "56") (name "Net-(T18-B)") (class "Default")
      (node (ref "R26") (pin "2") (pinfunction "2_2") (pintype "passive"))
      (node (ref "T18") (pin "2") (pinfunction "B_2") (pintype "passive"))
    )
    (net (code "57") (name "Net-(T19-B)") (class "Default")
      (node (ref "R28") (pin "2") (pinfunction "2_2") (pintype "passive"))
      (node (ref "T19") (pin "2") (pinfunction "B_2") (pintype "passive"))
    )
    (net (code "58") (name "Net-(T19-E)") (class "Default")
      (node (ref "T19") (pin "3") (pinfunction "E_3") (pintype "passive"))
      (node (ref "T20") (pin "1") (pinfunction "C_1") (pintype "passive"))
    )
    (net (code "59") (name "Net-(T20-B)") (class "Default")
      (node (ref "R29") (pin "2") (pinfunction "2_2") (pintype "passive"))
      (node (ref "T20") (pin "2") (pinfunction "B_2") (pintype "passive"))
    )
    (net (code "60") (name "Net-(T20-E)") (class "Default")
      (node (ref "T20") (pin "3") (pinfunction "E_3") (pintype "passive"))
      (node (ref "T21") (pin "1") (pinfunction "C_1") (pintype "passive"))
    )
    (net (code "61") (name "Net-(T21-B)") (class "Default")
      (node (ref "R31") (pin "2") (pinfunction "2_2") (pintype "passive"))
      (node (ref "T21") (pin "2") (pinfunction "B_2") (pintype "passive"))
    )
    (net (code "62") (name "Net-(T21-E)") (class "Default")
      (node (ref "T21") (pin "3") (pinfunction "E_3") (pintype "passive"))
      (node (ref "T22") (pin "1") (pinfunction "C_1") (pintype "passive"))
    )
    (net (code "63") (name "Net-(T22-B)") (class "Default")
      (node (ref "R32") (pin "2") (pinfunction "2_2") (pintype "passive"))
      (node (ref "T22") (pin "2") (pinfunction "B_2") (pintype "passive"))
    )
    (net (code "64") (name "Net-(T22-E)") (class "Default")
      (node (ref "T22") (pin "3") (pinfunction "E_3") (pintype "passive"))
      (node (ref "T23") (pin "1") (pinfunction "C_1") (pintype "passive"))
    )
    (net (code "65") (name "Net-(T23-B)") (class "Default")
      (node (ref "R33") (pin "2") (pinfunction "2_2") (pintype "passive"))
      (node (ref "T23") (pin "2") (pinfunction "B_2") (pintype "passive"))
    )
    (net (code "66") (name "Net-(T23-E)") (class "Default")
      (node (ref "T23") (pin "3") (pinfunction "E_3") (pintype "passive"))
      (node (ref "T24") (pin "1") (pinfunction "C_1") (pintype "passive"))
    )
    (net (code "67") (name "Net-(T24-B)") (class "Default")
      (node (ref "R34") (pin "2") (pinfunction "2_2") (pintype "passive"))
      (node (ref "T24") (pin "2") (pinfunction "B_2") (pintype "passive"))
    )
    (net (code "68") (name "Net-(T24-E)") (class "Default")
      (node (ref "T24") (pin "3") (pinfunction "E_3") (pintype "passive"))
      (node (ref "T27") (pin "1") (pinfunction "C_1") (pintype "passive"))
    )
    (net (code "69") (name "Net-(T25-B)") (class "Default")
      (node (ref "R35") (pin "2") (pinfunction "2_2") (pintype "passive"))
      (node (ref "T25") (pin "2") (pinfunction "B_2") (pintype "passive"))
    )
    (net (code "70") (name "Net-(T25-C)") (class "Default")
      (node (ref "R28") (pin "1") (pinfunction "1_1") (pintype "passive"))
      (node (ref "R37") (pin "1") (pinfunction "1_1") (pintype "passive"))
      (node (ref "T25") (pin "1") (pinfunction "C_1") (pintype "passive"))
    )
    (net (code "71") (name "Net-(T25-E)") (class "Default")
      (node (ref "T25") (pin "3") (pinfunction "E_3") (pintype "passive"))
      (node (ref "T26") (pin "1") (pinfunction "C_1") (pintype "passive"))
    )
    (net (code "72") (name "Net-(T26-B)") (class "Default")
      (node (ref "R36") (pin "2") (pinfunction "2_2") (pintype "passive"))
      (node (ref "T26") (pin "2") (pinfunction "B_2") (pintype "passive"))
    )
    (net (code "73") (name "Net-(T27-B)") (class "Default")
      (node (ref "R38") (pin "2") (pinfunction "2_2") (pintype "passive"))
      (node (ref "T27") (pin "2") (pinfunction "B_2") (pintype "passive"))
    )
    (net (code "74") (name "Net-(T28-B)") (class "Default")
      (node (ref "R40") (pin "2") (pinfunction "2_2") (pintype "passive"))
      (node (ref "T28") (pin "2") (pinfunction "B_2") (pintype "passive"))
    )
    (net (code "75") (name "Net-(T28-C)") (class "Default")
      (node (ref "T28") (pin "1") (pinfunction "C_1") (pintype "passive"))
      (node (ref "T29") (pin "3") (pinfunction "E_3") (pintype "passive"))
    )
    (net (code "76") (name "Net-(T29-B)") (class "Default")
      (node (ref "R39") (pin "2") (pinfunction "2_2") (pintype "passive"))
      (node (ref "T29") (pin "2") (pinfunction "B_2") (pintype "passive"))
    )
    (net (code "77") (name "Net-(T30-B)") (class "Default")
      (node (ref "R46") (pin "2") (pinfunction "2_2") (pintype "passive"))
      (node (ref "T30") (pin "2") (pinfunction "B_2") (pintype "passive"))
    )
    (net (code "78") (name "Net-(T30-C)") (class "Default")
      (node (ref "T30") (pin "1") (pinfunction "C_1") (pintype "passive"))
      (node (ref "T31") (pin "3") (pinfunction "E_3") (pintype "passive"))
    )
    (net (code "79") (name "Net-(T31-B)") (class "Default")
      (node (ref "R45") (pin "2") (pinfunction "2_2") (pintype "passive"))
      (node (ref "T31") (pin "2") (pinfunction "B_2") (pintype "passive"))
    )
    (net (code "80") (name "Net-(T31-C)") (class "Default")
      (node (ref "R47") (pin "1") (pinfunction "1_1") (pintype "passive"))
      (node (ref "R49") (pin "1") (pinfunction "1_1") (pintype "passive"))
      (node (ref "T31") (pin "1") (pinfunction "C_1") (pintype "passive"))
    )
    (net (code "81") (name "Net-(T32-B)") (class "Default")
      (node (ref "R43") (pin "2") (pinfunction "2_2") (pintype "passive"))
      (node (ref "T32") (pin "2") (pinfunction "B_2") (pintype "passive"))
    )
    (net (code "82") (name "Net-(T32-C)") (class "Default")
      (node (ref "T32") (pin "1") (pinfunction "C_1") (pintype "passive"))
      (node (ref "T33") (pin "3") (pinfunction "E_3") (pintype "passive"))
    )
    (net (code "83") (name "Net-(T33-B)") (class "Default")
      (node (ref "R42") (pin "2") (pinfunction "2_2") (pintype "passive"))
      (node (ref "T33") (pin "2") (pinfunction "B_2") (pintype "passive"))
    )
    (net (code "84") (name "Net-(T34-B)") (class "Default")
      (node (ref "R48") (pin "2") (pinfunction "2_2") (pintype "passive"))
      (node (ref "T34") (pin "2") (pinfunction "B_2") (pintype "passive"))
    )
    (net (code "85") (name "Net-(T34-C)") (class "Default")
      (node (ref "R50") (pin "1") (pinfunction "1_1") (pintype "passive"))
      (node (ref "R69") (pin "1") (pinfunction "1_1") (pintype "passive"))
      (node (ref "T34") (pin "1") (pinfunction "C_1") (pintype "passive"))
    )
    (net (code "86") (name "Net-(T34-E)") (class "Default")
      (node (ref "T34") (pin "3") (pinfunction "E_3") (pintype "passive"))
      (node (ref "T35") (pin "1") (pinfunction "C_1") (pintype "passive"))
    )
    (net (code "87") (name "Net-(T35-B)") (class "Default")
      (node (ref "R49") (pin "2") (pinfunction "2_2") (pintype "passive"))
      (node (ref "T35") (pin "2") (pinfunction "B_2") (pintype "passive"))
    )
    (net (code "88") (name "Net-(T36-B)") (class "Default")
      (node (ref "R55") (pin "2") (pinfunction "2_2") (pintype "passive"))
      (node (ref "T36") (pin "2") (pinfunction "B_2") (pintype "passive"))
    )
    (net (code "89") (name "Net-(T36-C)") (class "Default")
      (node (ref "T36") (pin "1") (pinfunction "C_1") (pintype "passive"))
      (node (ref "T37") (pin "3") (pinfunction "E_3") (pintype "passive"))
    )
    (net (code "90") (name "Net-(T37-B)") (class "Default")
      (node (ref "R54") (pin "2") (pinfunction "2_2") (pintype "passive"))
      (node (ref "T37") (pin "2") (pinfunction "B_2") (pintype "passive"))
    )
    (net (code "91") (name "Net-(T37-C)") (class "Default")
      (node (ref "R56") (pin "1") (pinfunction "1_1") (pintype "passive"))
      (node (ref "R58") (pin "1") (pinfunction "1_1") (pintype "passive"))
      (node (ref "T37") (pin "1") (pinfunction "C_1") (pintype "passive"))
    )
    (net (code "92") (name "Net-(T38-B)") (class "Default")
      (node (ref "R52") (pin "2") (pinfunction "2_2") (pintype "passive"))
      (node (ref "T38") (pin "2") (pinfunction "B_2") (pintype "passive"))
    )
    (net (code "93") (name "Net-(T38-C)") (class "Default")
      (node (ref "T38") (pin "1") (pinfunction "C_1") (pintype "passive"))
      (node (ref "T39") (pin "3") (pinfunction "E_3") (pintype "passive"))
    )
    (net (code "94") (name "Net-(T39-B)") (class "Default")
      (node (ref "R51") (pin "2") (pinfunction "2_2") (pintype "passive"))
      (node (ref "T39") (pin "2") (pinfunction "B_2") (pintype "passive"))
    )
    (net (code "95") (name "Net-(T39-C)") (class "Default")
      (node (ref "R53") (pin "2") (pinfunction "2_2") (pintype "passive"))
      (node (ref "R57") (pin "1") (pinfunction "1_1") (pintype "passive"))
      (node (ref "T39") (pin "1") (pinfunction "C_1") (pintype "passive"))
    )
    (net (code "96") (name "Net-(T40-B)") (class "Default")
      (node (ref "R57") (pin "2") (pinfunction "2_2") (pintype "passive"))
      (node (ref "T40") (pin "2") (pinfunction "B_2") (pintype "passive"))
    )
    (net (code "97") (name "Net-(T40-C)") (class "Default")
      (node (ref "R59") (pin "1") (pinfunction "1_1") (pintype "passive"))
      (node (ref "R72") (pin "1") (pinfunction "1_1") (pintype "passive"))
      (node (ref "T40") (pin "1") (pinfunction "C_1") (pintype "passive"))
    )
    (net (code "98") (name "Net-(T40-E)") (class "Default")
      (node (ref "T40") (pin "3") (pinfunction "E_3") (pintype "passive"))
      (node (ref "T41") (pin "1") (pinfunction "C_1") (pintype "passive"))
    )
    (net (code "99") (name "Net-(T41-B)") (class "Default")
      (node (ref "R58") (pin "2") (pinfunction "2_2") (pintype "passive"))
      (node (ref "T41") (pin "2") (pinfunction "B_2") (pintype "passive"))
    )
    (net (code "100") (name "Net-(T42-B)") (class "Default")
      (node (ref "R60") (pin "2") (pinfunction "2_2") (pintype "passive"))
      (node (ref "T42") (pin "2") (pinfunction "B_2") (pintype "passive"))
    )
    (net (code "101") (name "Net-(T43-B)") (class "Default")
      (node (ref "R62") (pin "2") (pinfunction "2_2") (pintype "passive"))
      (node (ref "T43") (pin "2") (pinfunction "B_2") (pintype "passive"))
    )
    (net (code "102") (name "Net-(T43-C)") (class "Default")
      (node (ref "R55") (pin "1") (pinfunction "1_1") (pintype "passive"))
      (node (ref "R63") (pin "2") (pinfunction "2_2") (pintype "passive"))
      (node (ref "T43") (pin "1") (pinfunction "C_1") (pintype "passive"))
    )
    (net (code "103") (name "Net-(T44-B)") (class "Default")
      (node (ref "R64") (pin "2") (pinfunction "2_2") (pintype "passive"))
      (node (ref "T44") (pin "2") (pinfunction "B_2") (pintype "passive"))
    )
    (net (code "104") (name "Net-(T44-E)") (class "Default")
      (node (ref "T44") (pin "3") (pinfunction "E_3") (pintype "passive"))
      (node (ref "T45") (pin "1") (pinfunction "C_1") (pintype "passive"))
    )
    (net (code "105") (name "Net-(T45-B)") (class "Default")
      (node (ref "R65") (pin "2") (pinfunction "2_2") (pintype "passive"))
      (node (ref "T45") (pin "2") (pinfunction "B_2") (pintype "passive"))
    )
    (net (code "106") (name "Net-(T45-E)") (class "Default")
      (node (ref "T45") (pin "3") (pinfunction "E_3") (pintype "passive"))
      (node (ref "T46") (pin "1") (pinfunction "C_1") (pintype "passive"))
    )
    (net (code "107") (name "Net-(T46-B)") (class "Default")
      (node (ref "R67") (pin "2") (pinfunction "2_2") (pintype "passive"))
      (node (ref "T46") (pin "2") (pinfunction "B_2") (pintype "passive"))
    )
    (net (code "108") (name "Net-(T46-E)") (class "Default")
      (node (ref "T46") (pin "3") (pinfunction "E_3") (pintype "passive"))
      (node (ref "T47") (pin "1") (pinfunction "C_1") (pintype "passive"))
    )
    (net (code "109") (name "Net-(T47-B)") (class "Default")
      (node (ref "R68") (pin "2") (pinfunction "2_2") (pintype "passive"))
      (node (ref "T47") (pin "2") (pinfunction "B_2") (pintype "passive"))
    )
    (net (code "110") (name "Net-(T48-B)") (class "Default")
      (node (ref "R69") (pin "2") (pinfunction "2_2") (pintype "passive"))
      (node (ref "T48") (pin "2") (pinfunction "B_2") (pintype "passive"))
    )
    (net (code "111") (name "Net-(T48-C)") (class "Default")
      (node (ref "R64") (pin "1") (pinfunction "1_1") (pintype "passive"))
      (node (ref "R71") (pin "1") (pinfunction "1_1") (pintype "passive"))
      (node (ref "T48") (pin "1") (pinfunction "C_1") (pintype "passive"))
    )
    (net (code "112") (name "Net-(T48-E)") (class "Default")
      (node (ref "T48") (pin "3") (pinfunction "E_3") (pintype "passive"))
      (node (ref "T49") (pin "1") (pinfunction "C_1") (pintype "passive"))
    )
    (net (code "113") (name "Net-(T49-B)") (class "Default")
      (node (ref "R70") (pin "2") (pinfunction "2_2") (pintype "passive"))
      (node (ref "T49") (pin "2") (pinfunction "B_2") (pintype "passive"))
    )
    (net (code "114") (name "Net-(T50-B)") (class "Default")
      (node (ref "R72") (pin "2") (pinfunction "2_2") (pintype "passive"))
      (node (ref "T50") (pin "2") (pinfunction "B_2") (pintype "passive"))
    )
    (net (code "115") (name "Net-(T50-C)") (class "Default")
      (node (ref "R65") (pin "1") (pinfunction "1_1") (pintype "passive"))
      (node (ref "R74") (pin "1") (pinfunction "1_1") (pintype "passive"))
      (node (ref "T50") (pin "1") (pinfunction "C_1") (pintype "passive"))
    )
    (net (code "116") (name "Net-(T50-E)") (class "Default")
      (node (ref "T50") (pin "3") (pinfunction "E_3") (pintype "passive"))
      (node (ref "T51") (pin "1") (pinfunction "C_1") (pintype "passive"))
    )
    (net (code "117") (name "Net-(T51-B)") (class "Default")
      (node (ref "R73") (pin "2") (pinfunction "2_2") (pintype "passive"))
      (node (ref "T51") (pin "2") (pinfunction "B_2") (pintype "passive"))
    )
    (net (code "118") (name "Net-(T52-B)") (class "Default")
      (node (ref "R75") (pin "2") (pinfunction "2_2") (pintype "passive"))
      (node (ref "T52") (pin "2") (pinfunction "B_2") (pintype "passive"))
    )
    (net (code "119") (name "Net-(T52-C)") (class "Default")
      (node (ref "R67") (pin "1") (pinfunction "1_1") (pintype "passive"))
      (node (ref "R85") (pin "1") (pinfunction "1_1") (pintype "passive"))
      (node (ref "T52") (pin "1") (pinfunction "C_1") (pintype "passive"))
    )
    (net (code "120") (name "Net-(T52-E)") (class "Default")
      (node (ref "T52") (pin "3") (pinfunction "E_3") (pintype "passive"))
      (node (ref "T58") (pin "1") (pinfunction "C_1") (pintype "passive"))
    )
    (net (code "121") (name "Net-(T53-B)") (class "Default")
      (node (ref "R77") (pin "2") (pinfunction "2_2") (pintype "passive"))
      (node (ref "T53") (pin "2") (pinfunction "B_2") (pintype "passive"))
    )
    (net (code "122") (name "Net-(T53-C)") (class "Default")
      (node (ref "R31") (pin "1") (pinfunction "1_1") (pintype "passive"))
      (node (ref "R79") (pin "1") (pinfunction "1_1") (pintype "passive"))
      (node (ref "T53") (pin "1") (pinfunction "C_1") (pintype "passive"))
    )
    (net (code "123") (name "Net-(T53-E)") (class "Default")
      (node (ref "T53") (pin "3") (pinfunction "E_3") (pintype "passive"))
      (node (ref "T54") (pin "1") (pinfunction "C_1") (pintype "passive"))
    )
    (net (code "124") (name "Net-(T54-B)") (class "Default")
      (node (ref "R78") (pin "2") (pinfunction "2_2") (pintype "passive"))
      (node (ref "T54") (pin "2") (pinfunction "B_2") (pintype "passive"))
    )
    (net (code "125") (name "Net-(T55-B)") (class "Default")
      (node (ref "R80") (pin "2") (pinfunction "2_2") (pintype "passive"))
      (node (ref "T55") (pin "2") (pinfunction "B_2") (pintype "passive"))
    )
    (net (code "126") (name "Net-(T55-C)") (class "Default")
      (node (ref "R32") (pin "1") (pinfunction "1_1") (pintype "passive"))
      (node (ref "R82") (pin "1") (pinfunction "1_1") (pintype "passive"))
      (node (ref "T55") (pin "1") (pinfunction "C_1") (pintype "passive"))
    )
    (net (code "127") (name "Net-(T55-E)") (class "Default")
      (node (ref "T55") (pin "3") (pinfunction "E_3") (pintype "passive"))
      (node (ref "T56") (pin "1") (pinfunction "C_1") (pintype "passive"))
    )
    (net (code "128") (name "Net-(T56-B)") (class "Default")
      (node (ref "R81") (pin "2") (pinfunction "2_2") (pintype "passive"))
      (node (ref "T56") (pin "2") (pinfunction "B_2") (pintype "passive"))
    )
    (net (code "129") (name "Net-(T57-B)") (class "Default")
      (node (ref "R83") (pin "2") (pinfunction "2_2") (pintype "passive"))
      (node (ref "T57") (pin "2") (pinfunction "B_2") (pintype "passive"))
    )
    (net (code "130") (name "Net-(T57-C)") (class "Default")
      (node (ref "R80") (pin "1") (pinfunction "1_1") (pintype "passive"))
      (node (ref "R84") (pin "1") (pinfunction "1_1") (pintype "passive"))
      (node (ref "T57") (pin "1") (pinfunction "C_1") (pintype "passive"))
    )
    (net (code "131") (name "Net-(T58-B)") (class "Default")
      (node (ref "R76") (pin "2") (pinfunction "2_2") (pintype "passive"))
      (node (ref "T58") (pin "2") (pinfunction "B_2") (pintype "passive"))
    )
    (net (code "132") (name "Net-(T59-B)") (class "Default")
      (node (ref "R86") (pin "2") (pinfunction "2_2") (pintype "passive"))
      (node (ref "T59") (pin "2") (pinfunction "B_2") (pintype "passive"))
    )
    (net (code "133") (name "Net-(T59-C)") (class "Default")
      (node (ref "R68") (pin "1") (pinfunction "1_1") (pintype "passive"))
      (node (ref "R88") (pin "1") (pinfunction "1_1") (pintype "passive"))
      (node (ref "T59") (pin "1") (pinfunction "C_1") (pintype "passive"))
    )
    (net (code "134") (name "Net-(T59-E)") (class "Default")
      (node (ref "T59") (pin "3") (pinfunction "E_3") (pintype "passive"))
      (node (ref "T60") (pin "1") (pinfunction "C_1") (pintype "passive"))
    )
    (net (code "135") (name "Net-(T60-B)") (class "Default")
      (node (ref "R87") (pin "2") (pinfunction "2_2") (pintype "passive"))
      (node (ref "T60") (pin "2") (pinfunction "B_2") (pintype "passive"))
    )
    (net (code "136") (name "Net-(T61-B)") (class "Default")
      (node (ref "R89") (pin "2") (pinfunction "2_2") (pintype "passive"))
      (node (ref "T61") (pin "2") (pinfunction "B_2") (pintype "passive"))
    )
    (net (code "137") (name "Net-(T61-E)") (class "Default")
      (node (ref "T61") (pin "3") (pinfunction "E_3") (pintype "passive"))
      (node (ref "T62") (pin "1") (pinfunction "C_1") (pintype "passive"))
    )
    (net (code "138") (name "Net-(T62-B)") (class "Default")
      (node (ref "R90") (pin "2") (pinfunction "2_2") (pintype "passive"))
      (node (ref "T62") (pin "2") (pinfunction "B_2") (pintype "passive"))
    )
    (net (code "139") (name "Net-(T63-B)") (class "Default")
      (node (ref "R92") (pin "2") (pinfunction "2_2") (pintype "passive"))
      (node (ref "T63") (pin "2") (pinfunction "B_2") (pintype "passive"))
    )
    (net (code "140") (name "Net-(T63-E)") (class "Default")
      (node (ref "T63") (pin "3") (pinfunction "E_3") (pintype "passive"))
      (node (ref "T64") (pin "1") (pinfunction "C_1") (pintype "passive"))
    )
    (net (code "141") (name "Net-(T64-B)") (class "Default")
      (node (ref "R93") (pin "2") (pinfunction "2_2") (pintype "passive"))
      (node (ref "T64") (pin "2") (pinfunction "B_2") (pintype "passive"))
    )
    (net (code "142") (name "Net-(T65-B)") (class "Default")
      (node (ref "R95") (pin "2") (pinfunction "2_2") (pintype "passive"))
      (node (ref "T65") (pin "2") (pinfunction "B_2") (pintype "passive"))
    )
    (net (code "143") (name "Net-(T66-B)") (class "Default")
      (node (ref "R97") (pin "2") (pinfunction "2_2") (pintype "passive"))
      (node (ref "T66") (pin "2") (pinfunction "B_2") (pintype "passive"))
    )
    (net (code "144") (name "RC") (class "Default")
      (node (ref "R92") (pin "1") (pinfunction "1_1") (pintype "passive"))
      (node (ref "X7") (pin "5") (pinfunction "S_5") (pintype "passive"))
    )
    (net (code "145") (name "RSH") (class "Default")
      (node (ref "R87") (pin "1") (pinfunction "1_1") (pintype "passive"))
      (node (ref "R93") (pin "1") (pinfunction "1_1") (pintype "passive"))
      (node (ref "X1") (pin "5") (pinfunction "S_5") (pintype "passive"))
    )
    (net (code "146") (name "SO") (class "Default")
      (node (ref "R30") (pin "1") (pinfunction "1_1") (pintype "passive"))
      (node (ref "R95") (pin "1") (pinfunction "1_1") (pintype "passive"))
      (node (ref "T19") (pin "1") (pinfunction "C_1") (pintype "passive"))
      (node (ref "X1") (pin "8") (pinfunction "S_8") (pintype "passive"))
    )
    (net (code "147") (name "SUB") (class "Default")
      (node (ref "R73") (pin "1") (pinfunction "1_1") (pintype "passive"))
      (node (ref "X7") (pin "8") (pinfunction "S_8") (pintype "passive"))
    )
    (net (code "148") (name "VCC") (class "Default")
      (node (ref "R12") (pin "2") (pinfunction "2_2") (pintype "passive"))
      (node (ref "R15") (pin "2") (pinfunction "2_2") (pintype "passive"))
      (node (ref "R18") (pin "1") (pinfunction "1_1") (pintype "passive"))
      (node (ref "R21") (pin "2") (pinfunction "2_2") (pintype "passive"))
      (node (ref "R24") (pin "2") (pinfunction "2_2") (pintype "passive"))
      (node (ref "R27") (pin "2") (pinfunction "2_2") (pintype "passive"))
      (node (ref "R3") (pin "2") (pinfunction "2_2") (pintype "passive"))
      (node (ref "R30") (pin "2") (pinfunction "2_2") (pintype "passive"))
      (node (ref "R37") (pin "2") (pinfunction "2_2") (pintype "passive"))
      (node (ref "R41") (pin "2") (pinfunction "2_2") (pintype "passive"))
      (node (ref "R44") (pin "1") (pinfunction "1_1") (pintype "passive"))
      (node (ref "R47") (pin "2") (pinfunction "2_2") (pintype "passive"))
      (node (ref "R50") (pin "2") (pinfunction "2_2") (pintype "passive"))
      (node (ref "R53") (pin "1") (pinfunction "1_1") (pintype "passive"))
      (node (ref "R56") (pin "2") (pinfunction "2_2") (pintype "passive"))
      (node (ref "R59") (pin "2") (pinfunction "2_2") (pintype "passive"))
      (node (ref "R6") (pin "1") (pinfunction "1_1") (pintype "passive"))
      (node (ref "R61") (pin "1") (pinfunction "1_1") (pintype "passive"))
      (node (ref "R63") (pin "1") (pinfunction "1_1") (pintype "passive"))
      (node (ref "R66") (pin "2") (pinfunction "2_2") (pintype "passive"))
      (node (ref "R71") (pin "2") (pinfunction "2_2") (pintype "passive"))
      (node (ref "R74") (pin "2") (pinfunction "2_2") (pintype "passive"))
      (node (ref "R79") (pin "2") (pinfunction "2_2") (pintype "passive"))
      (node (ref "R82") (pin "2") (pinfunction "2_2") (pintype "passive"))
      (node (ref "R84") (pin "2") (pinfunction "2_2") (pintype "passive"))
      (node (ref "R85") (pin "2") (pinfunction "2_2") (pintype "passive"))
      (node (ref "R88") (pin "2") (pinfunction "2_2") (pintype "passive"))
      (node (ref "R9") (pin "2") (pinfunction "2_2") (pintype "passive"))
      (node (ref "R91") (pin "2") (pinfunction "2_2") (pintype "passive"))
      (node (ref "R94") (pin "2") (pinfunction "2_2") (pintype "passive"))
      (node (ref "R96") (pin "2") (pinfunction "2_2") (pintype "passive"))
      (node (ref "R98") (pin "2") (pinfunction "2_2") (pintype "passive"))
      (node (ref "X7") (pin "1") (pinfunction "S_1") (pintype "passive"))
    )
    (net (code "149") (name "XOR") (class "Default")
      (node (ref "R36") (pin "1") (pinfunction "1_1") (pintype "passive"))
      (node (ref "X1") (pin "2") (pinfunction "S_2") (pintype "passive"))
    )
  )
)
